# FLEXQCMV2_1.net
KiCad netlist of a schematic drawn in EAGLE
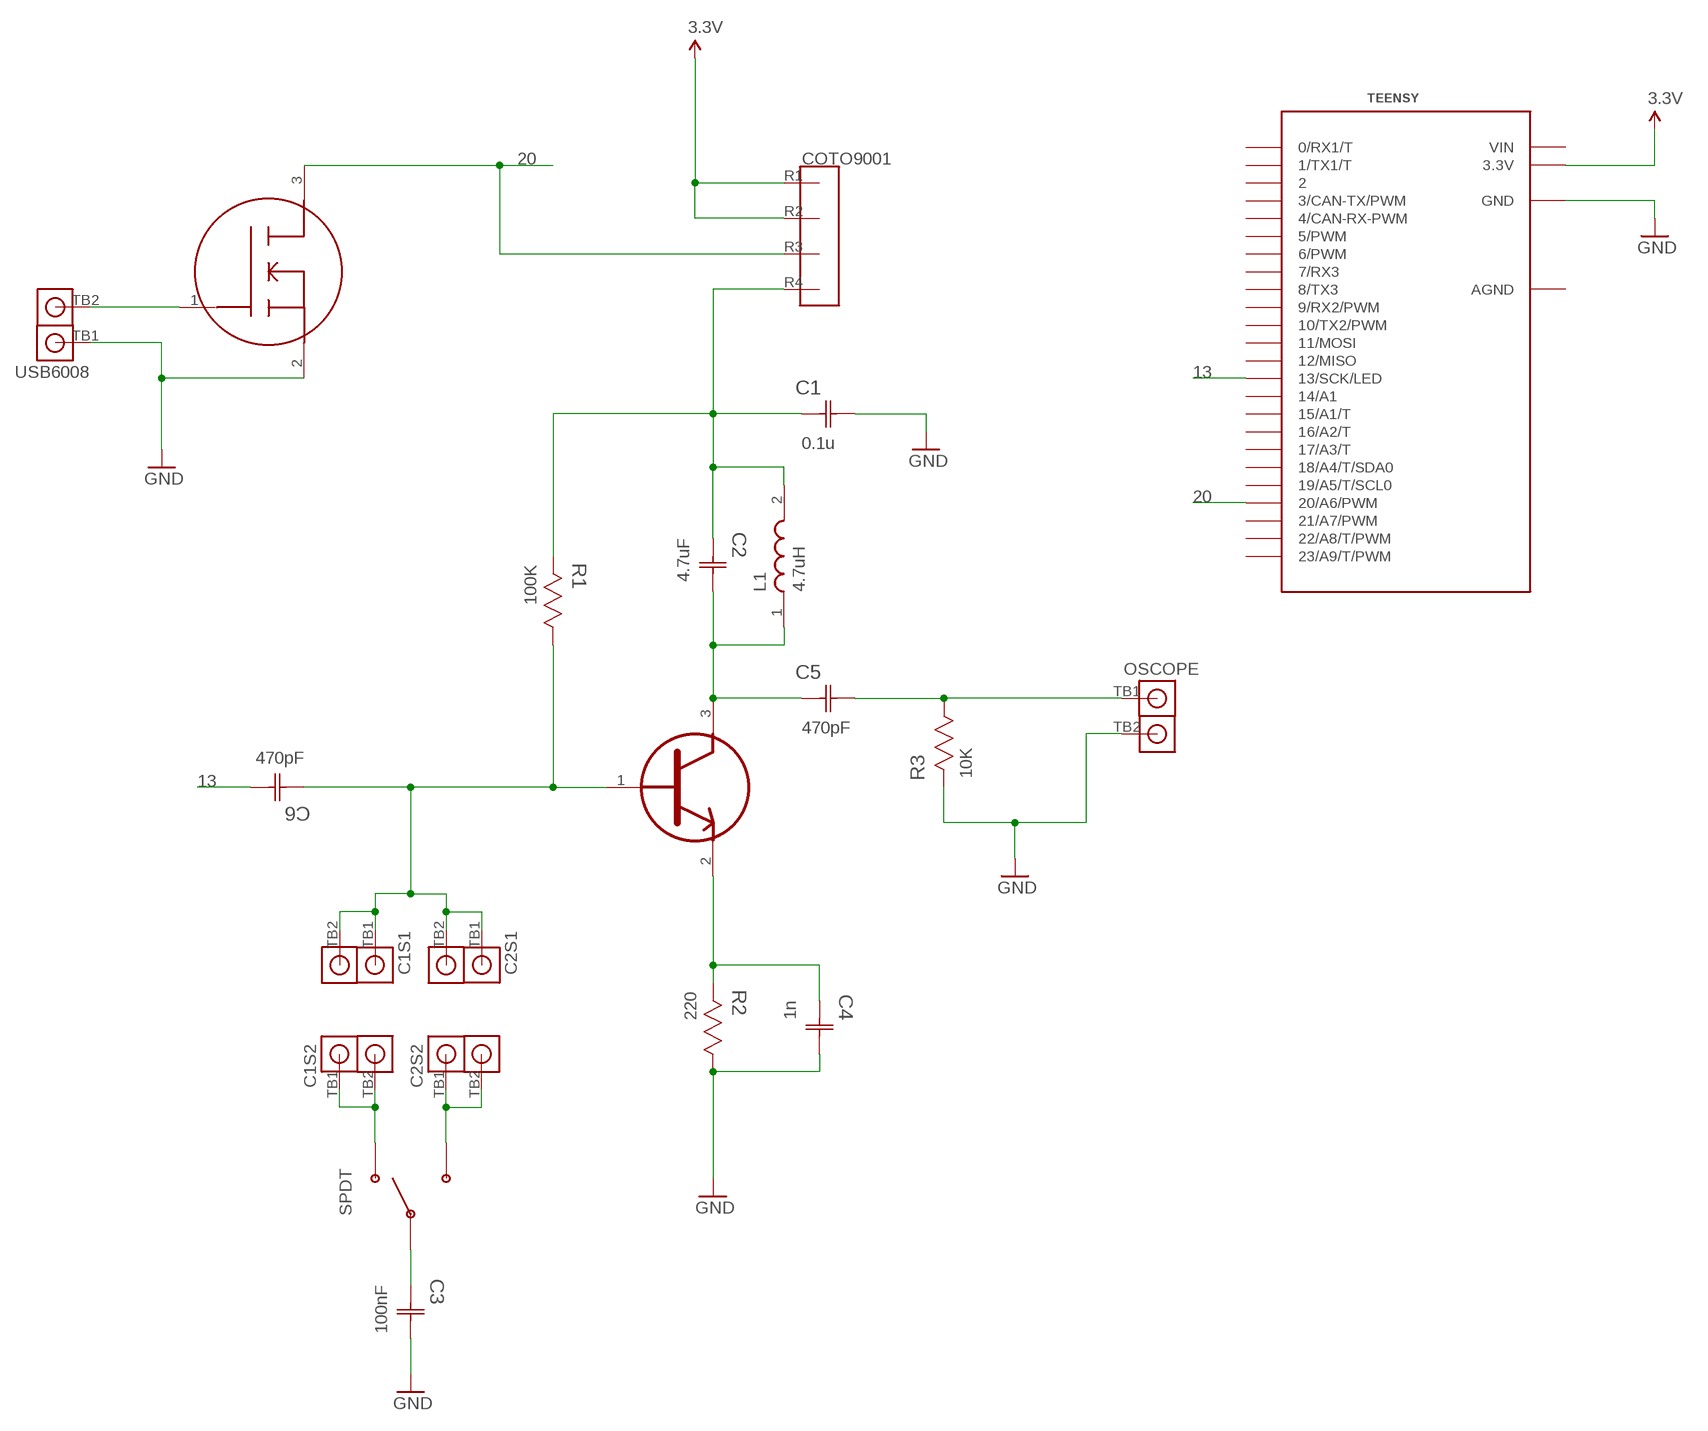
[diagram p0: schematic, sheet 1]

(export (version "E")
  (design (tool "Eeschema 10.0.6"))
  (components
    (comp (ref "C1")
      (value "0.1u")
      (footprint "eagle-import:CAPC3216X88N")
      (fields (field (name "MPN") "C1206C104K1RACTU") (field (name "TOLERANCE") "±10%"))
      (libsource (lib "eagle-import") (part "C1206C104K1RACTU"))
    )
    (comp (ref "C1S1")
      (value "TERMBLOCKX2")
      (footprint "eagle-import:TERMBLOCKX2")
      (libsource (lib "eagle-import") (part "TERMBLOCKX2"))
    )
    (comp (ref "C1S2")
      (value "TERMBLOCKX2")
      (footprint "eagle-import:TERMBLOCKX2")
      (libsource (lib "eagle-import") (part "TERMBLOCKX2"))
    )
    (comp (ref "C2")
      (value "4.7uF")
      (footprint "eagle-import:CAPC3216X180N")
      (fields (field (name "MPN") "C1206C475K3RACTU") (field (name "TOLERANCE") "±10%"))
      (libsource (lib "eagle-import") (part "C1206C475K3RACTU"))
    )
    (comp (ref "C2S1")
      (value "TERMBLOCKX2")
      (footprint "eagle-import:TERMBLOCKX2")
      (libsource (lib "eagle-import") (part "TERMBLOCKX2"))
    )
    (comp (ref "C2S2")
      (value "TERMBLOCKX2")
      (footprint "eagle-import:TERMBLOCKX2")
      (libsource (lib "eagle-import") (part "TERMBLOCKX2"))
    )
    (comp (ref "C3")
      (value "100nF")
      (footprint "eagle-import:CAPC3216X88N")
      (fields (field (name "MPN") "C1206C104K1RACTU") (field (name "TOLERANCE") "±10%"))
      (libsource (lib "eagle-import") (part "C1206C104K1RACTU"))
    )
    (comp (ref "C4")
      (value "1n")
      (footprint "eagle-import:CAPC3216X88N")
      (fields (field (name "MPN") "C1206C103K5RACTU") (field (name "TOLERANCE") "±10%"))
      (libsource (lib "eagle-import") (part "C1206C103K5RACTU"))
    )
    (comp (ref "C5")
      (value "470pF")
      (footprint "eagle-import:CAPC3216X100N")
      (fields (field (name "MPN") "C1206C474K3RACTU") (field (name "TOLERANCE") "±10%"))
      (libsource (lib "eagle-import") (part "C1206C474K3RACTU"))
    )
    (comp (ref "C6")
      (value "470pF")
      (footprint "eagle-import:CAPC3216X100N")
      (fields (field (name "MPN") "C1206C474K3RACTU") (field (name "TOLERANCE") "±10%"))
      (libsource (lib "eagle-import") (part "C1206C474K3RACTU"))
    )
    (comp (ref "COTO9001")
      (value "COTO9001")
      (footprint "eagle-import:COTO9001")
      (libsource (lib "eagle-import") (part "COTO9001"))
    )
    (comp (ref "L1")
      (value "4.7uH")
      (footprint "eagle-import:INDC3225X210N")
      (fields (field (name "MPN") "B82422A1472K100") (field (name "TOLERANCE") "±10%"))
      (libsource (lib "eagle-import") (part "B82422A1472K100"))
    )
    (comp (ref "OSCOPE")
      (value "TERMBLOCKX2")
      (footprint "eagle-import:TERMBLOCKX2")
      (libsource (lib "eagle-import") (part "TERMBLOCKX2"))
    )
    (comp (ref "R1")
      (value "100K")
      (footprint "eagle-import:RESC3216X71N")
      (fields (field (name "MPN") "CRCW1206100KJNEA") (field (name "TOLERANCE") "±5%"))
      (libsource (lib "eagle-import") (part "CRCW1206100KJNEA"))
    )
    (comp (ref "R2")
      (value "220")
      (footprint "eagle-import:RESC3216X71N")
      (fields (field (name "MPN") "CRCW1206220RJNEA") (field (name "TOLERANCE") "±5%"))
      (libsource (lib "eagle-import") (part "CRCW1206220RJNEA"))
    )
    (comp (ref "R3")
      (value "10K")
      (footprint "eagle-import:RESC3216X71N")
      (fields (field (name "MPN") "CRCW120610K0FKEA") (field (name "TOLERANCE") "±1%"))
      (libsource (lib "eagle-import") (part "CRCW120610K0FKEA"))
    )
    (comp (ref "SPDT")
      (value "SPDTSWITCH")
      (footprint "eagle-import:SPDTSWITCH")
      (libsource (lib "eagle-import") (part "SPDTSWITCH"))
    )
    (comp (ref "TEENSY")
      (value "TEENSY_3.1_DIL")
      (footprint "eagle-import:TEENSY3-DIL")
      (libsource (lib "eagle-import") (part "TEENSY_3.1_DIL"))
    )
    (comp (ref "U1")
      (value "FET")
      (footprint "eagle-import:SOT95P230X110-3N")
      (fields (field (name "MPN") "2N7002K"))
      (libsource (lib "eagle-import") (part "2N7002K"))
    )
    (comp (ref "U2")
      (value "BJT")
      (footprint "eagle-import:SOT95P230X110-3N")
      (libsource (lib "eagle-import") (part "BC847C"))
    )
    (comp (ref "USB6008")
      (value "TERMBLOCKX2")
      (footprint "eagle-import:TERMBLOCKX2")
      (libsource (lib "eagle-import") (part "TERMBLOCKX2"))
    )
  )
  (nets
    (net (code "1") (name "/13") (class "Default")
      (node (ref "C6") (pin "2") (pinfunction "C2_2") (pintype "passive"))
      (node (ref "TEENSY") (pin "13") (pinfunction "13/SCK/LED_13") (pintype "bidirectional"))
    )
    (net (code "2") (name "/20") (class "Default")
      (node (ref "COTO9001") (pin "R3") (pinfunction "R3_R3") (pintype "bidirectional"))
      (node (ref "TEENSY") (pin "20/A6") (pinfunction "20/A6/PWM_20/A6") (pintype "bidirectional"))
      (node (ref "U1") (pin "3") (pinfunction "D_3") (pintype "bidirectional"))
    )
    (net (code "3") (name "/AGND") (class "Default")
      (node (ref "TEENSY") (pin "AGND") (pinfunction "AGND_AGND") (pintype "power_in"))
    )
    (net (code "4") (name "/VIN") (class "Default")
      (node (ref "TEENSY") (pin "VIN") (pinfunction "VIN_VIN") (pintype "power_in"))
    )
    (net (code "5") (name "3.3V") (class "Default")
      (node (ref "COTO9001") (pin "R1") (pinfunction "R1_R1") (pintype "bidirectional"))
      (node (ref "COTO9001") (pin "R2") (pinfunction "R2_R2") (pintype "bidirectional"))
      (node (ref "TEENSY") (pin "3.3V") (pinfunction "3.3V_3.3V") (pintype "power_in"))
    )
    (net (code "6") (name "GND") (class "Default")
      (node (ref "C1") (pin "2") (pinfunction "C2_2") (pintype "passive"))
      (node (ref "C3") (pin "2") (pinfunction "C2_2") (pintype "passive"))
      (node (ref "C4") (pin "2") (pinfunction "C2_2") (pintype "passive"))
      (node (ref "OSCOPE") (pin "TB2") (pinfunction "TB2_TB2") (pintype "bidirectional"))
      (node (ref "R2") (pin "1") (pinfunction "1_1") (pintype "passive"))
      (node (ref "R3") (pin "2") (pinfunction "2_2") (pintype "passive"))
      (node (ref "TEENSY") (pin "GND") (pinfunction "GND_GND") (pintype "power_in"))
      (node (ref "U1") (pin "2") (pinfunction "S_2") (pintype "bidirectional"))
      (node (ref "USB6008") (pin "TB1") (pinfunction "TB1_TB1") (pintype "bidirectional"))
    )
    (net (code "7") (name "Net-(C1-C1)") (class "Default")
      (node (ref "C1") (pin "1") (pinfunction "C1_1") (pintype "passive"))
      (node (ref "C2") (pin "1") (pinfunction "C1_1") (pintype "passive"))
      (node (ref "COTO9001") (pin "R4") (pinfunction "R4_R4") (pintype "bidirectional"))
      (node (ref "L1") (pin "2") (pinfunction "P$2_2") (pintype "bidirectional"))
      (node (ref "R1") (pin "2") (pinfunction "2_2") (pintype "passive"))
    )
    (net (code "8") (name "Net-(C1S2-PadTB1)") (class "Default")
      (node (ref "C1S2") (pin "TB1") (pinfunction "TB1_TB1") (pintype "bidirectional"))
      (node (ref "C1S2") (pin "TB2") (pinfunction "TB2_TB2") (pintype "bidirectional"))
      (node (ref "SPDT") (pin "SW1") (pinfunction "SW1_SW1") (pintype "bidirectional"))
    )
    (net (code "9") (name "Net-(C2-C2)") (class "Default")
      (node (ref "C2") (pin "2") (pinfunction "C2_2") (pintype "passive"))
      (node (ref "C5") (pin "1") (pinfunction "C1_1") (pintype "passive"))
      (node (ref "L1") (pin "1") (pinfunction "P$1_1") (pintype "bidirectional"))
      (node (ref "U2") (pin "3") (pinfunction "C_3") (pintype "bidirectional"))
    )
    (net (code "10") (name "Net-(C2S2-PadTB1)") (class "Default")
      (node (ref "C2S2") (pin "TB1") (pinfunction "TB1_TB1") (pintype "bidirectional"))
      (node (ref "C2S2") (pin "TB2") (pinfunction "TB2_TB2") (pintype "bidirectional"))
      (node (ref "SPDT") (pin "SW3") (pinfunction "SW3_SW3") (pintype "bidirectional"))
    )
    (net (code "11") (name "Net-(C3-C1)") (class "Default")
      (node (ref "C3") (pin "1") (pinfunction "C1_1") (pintype "passive"))
      (node (ref "SPDT") (pin "SW2") (pinfunction "SW2_SW2") (pintype "bidirectional"))
    )
    (net (code "12") (name "Net-(C4-C1)") (class "Default")
      (node (ref "C4") (pin "1") (pinfunction "C1_1") (pintype "passive"))
      (node (ref "R2") (pin "2") (pinfunction "2_2") (pintype "passive"))
      (node (ref "U2") (pin "2") (pinfunction "E_2") (pintype "bidirectional"))
    )
    (net (code "13") (name "Net-(C5-C2)") (class "Default")
      (node (ref "C5") (pin "2") (pinfunction "C2_2") (pintype "passive"))
      (node (ref "OSCOPE") (pin "TB1") (pinfunction "TB1_TB1") (pintype "bidirectional"))
      (node (ref "R3") (pin "1") (pinfunction "1_1") (pintype "passive"))
    )
    (net (code "14") (name "Net-(C6-C1)") (class "Default")
      (node (ref "C1S1") (pin "TB1") (pinfunction "TB1_TB1") (pintype "bidirectional"))
      (node (ref "C1S1") (pin "TB2") (pinfunction "TB2_TB2") (pintype "bidirectional"))
      (node (ref "C2S1") (pin "TB1") (pinfunction "TB1_TB1") (pintype "bidirectional"))
      (node (ref "C2S1") (pin "TB2") (pinfunction "TB2_TB2") (pintype "bidirectional"))
      (node (ref "C6") (pin "1") (pinfunction "C1_1") (pintype "passive"))
      (node (ref "R1") (pin "1") (pinfunction "1_1") (pintype "passive"))
      (node (ref "U2") (pin "1") (pinfunction "B_1") (pintype "bidirectional"))
    )
    (net (code "15") (name "Net-(U1-G)") (class "Default")
      (node (ref "U1") (pin "1") (pinfunction "G_1") (pintype "bidirectional"))
      (node (ref "USB6008") (pin "TB2") (pinfunction "TB2_TB2") (pintype "bidirectional"))
    )
    (net (code "16") (name "unconnected-(TEENSY-0{slash}RX1{slash}T-Pad0)") (class "Default")
      (node (ref "TEENSY") (pin "0") (pinfunction "0/RX1/T_0") (pintype "bidirectional"))
    )
    (net (code "17") (name "unconnected-(TEENSY-1{slash}TX1{slash}T-Pad1)") (class "Default")
      (node (ref "TEENSY") (pin "1") (pinfunction "1/TX1/T_1") (pintype "bidirectional"))
    )
    (net (code "18") (name "unconnected-(TEENSY-3{slash}CAN-TX{slash}PWM-Pad3)") (class "Default")
      (node (ref "TEENSY") (pin "3") (pinfunction "3/CAN-TX/PWM_3") (pintype "bidirectional"))
    )
    (net (code "19") (name "unconnected-(TEENSY-4{slash}CAN-RX-PWM-Pad4)") (class "Default")
      (node (ref "TEENSY") (pin "4") (pinfunction "4/CAN-RX-PWM_4") (pintype "bidirectional"))
    )
    (net (code "20") (name "unconnected-(TEENSY-5{slash}PWM-Pad5)") (class "Default")
      (node (ref "TEENSY") (pin "5") (pinfunction "5/PWM_5") (pintype "bidirectional"))
    )
    (net (code "21") (name "unconnected-(TEENSY-6{slash}PWM-Pad6)") (class "Default")
      (node (ref "TEENSY") (pin "6") (pinfunction "6/PWM_6") (pintype "bidirectional"))
    )
    (net (code "22") (name "unconnected-(TEENSY-7{slash}RX3-Pad7)") (class "Default")
      (node (ref "TEENSY") (pin "7") (pinfunction "7/RX3_7") (pintype "bidirectional"))
    )
    (net (code "23") (name "unconnected-(TEENSY-8{slash}TX3-Pad8)") (class "Default")
      (node (ref "TEENSY") (pin "8") (pinfunction "8/TX3_8") (pintype "bidirectional"))
    )
    (net (code "24") (name "unconnected-(TEENSY-9{slash}RX2{slash}PWM-Pad9)") (class "Default")
      (node (ref "TEENSY") (pin "9") (pinfunction "9/RX2/PWM_9") (pintype "bidirectional"))
    )
    (net (code "25") (name "unconnected-(TEENSY-10{slash}TX2{slash}PWM-Pad10)") (class "Default")
      (node (ref "TEENSY") (pin "10") (pinfunction "10/TX2/PWM_10") (pintype "bidirectional"))
    )
    (net (code "26") (name "unconnected-(TEENSY-11{slash}MOSI-Pad11)") (class "Default")
      (node (ref "TEENSY") (pin "11") (pinfunction "11/MOSI_11") (pintype "bidirectional"))
    )
    (net (code "27") (name "unconnected-(TEENSY-12{slash}MISO-Pad12)") (class "Default")
      (node (ref "TEENSY") (pin "12") (pinfunction "12/MISO_12") (pintype "bidirectional"))
    )
    (net (code "28") (name "unconnected-(TEENSY-14{slash}A1-Pad14{slash}A0)") (class "Default")
      (node (ref "TEENSY") (pin "14/A0") (pinfunction "14/A1_14/A0") (pintype "bidirectional"))
    )
    (net (code "29") (name "unconnected-(TEENSY-15{slash}A1{slash}T-Pad15{slash}A1)") (class "Default")
      (node (ref "TEENSY") (pin "15/A1") (pinfunction "15/A1/T_15/A1") (pintype "bidirectional"))
    )
    (net (code "30") (name "unconnected-(TEENSY-16{slash}A2{slash}T-Pad16{slash}A2)") (class "Default")
      (node (ref "TEENSY") (pin "16/A2") (pinfunction "16/A2/T_16/A2") (pintype "bidirectional"))
    )
    (net (code "31") (name "unconnected-(TEENSY-17{slash}A3{slash}T-Pad17{slash}A3)") (class "Default")
      (node (ref "TEENSY") (pin "17/A3") (pinfunction "17/A3/T_17/A3") (pintype "bidirectional"))
    )
    (net (code "32") (name "unconnected-(TEENSY-18{slash}A4{slash}T{slash}SDA0-Pad18{slash}A4)") (class "Default")
      (node (ref "TEENSY") (pin "18/A4") (pinfunction "18/A4/T/SDA0_18/A4") (pintype "bidirectional"))
    )
    (net (code "33") (name "unconnected-(TEENSY-19{slash}A5{slash}T{slash}SCL0-Pad19{slash}A5)") (class "Default")
      (node (ref "TEENSY") (pin "19/A5") (pinfunction "19/A5/T/SCL0_19/A5") (pintype "bidirectional"))
    )
    (net (code "34") (name "unconnected-(TEENSY-21{slash}A7{slash}PWM-Pad21{slash}A7)") (class "Default")
      (node (ref "TEENSY") (pin "21/A7") (pinfunction "21/A7/PWM_21/A7") (pintype "bidirectional"))
    )
    (net (code "35") (name "unconnected-(TEENSY-22{slash}A8{slash}T{slash}PWM-Pad22{slash}A8)") (class "Default")
      (node (ref "TEENSY") (pin "22/A8") (pinfunction "22/A8/T/PWM_22/A8") (pintype "bidirectional"))
    )
    (net (code "36") (name "unconnected-(TEENSY-23{slash}A9{slash}T{slash}PWM-Pad23{slash}A9)") (class "Default")
      (node (ref "TEENSY") (pin "23/A9") (pinfunction "23/A9/T/PWM_23/A9") (pintype "bidirectional"))
    )
    (net (code "37") (name "unconnected-(TEENSY-Pad2)") (class "Default")
      (node (ref "TEENSY") (pin "2") (pinfunction "2_2") (pintype "bidirectional"))
    )
  )
)
